# Block_Manager_Rev_D1.net
KiCad netlist of a schematic drawn in EAGLE
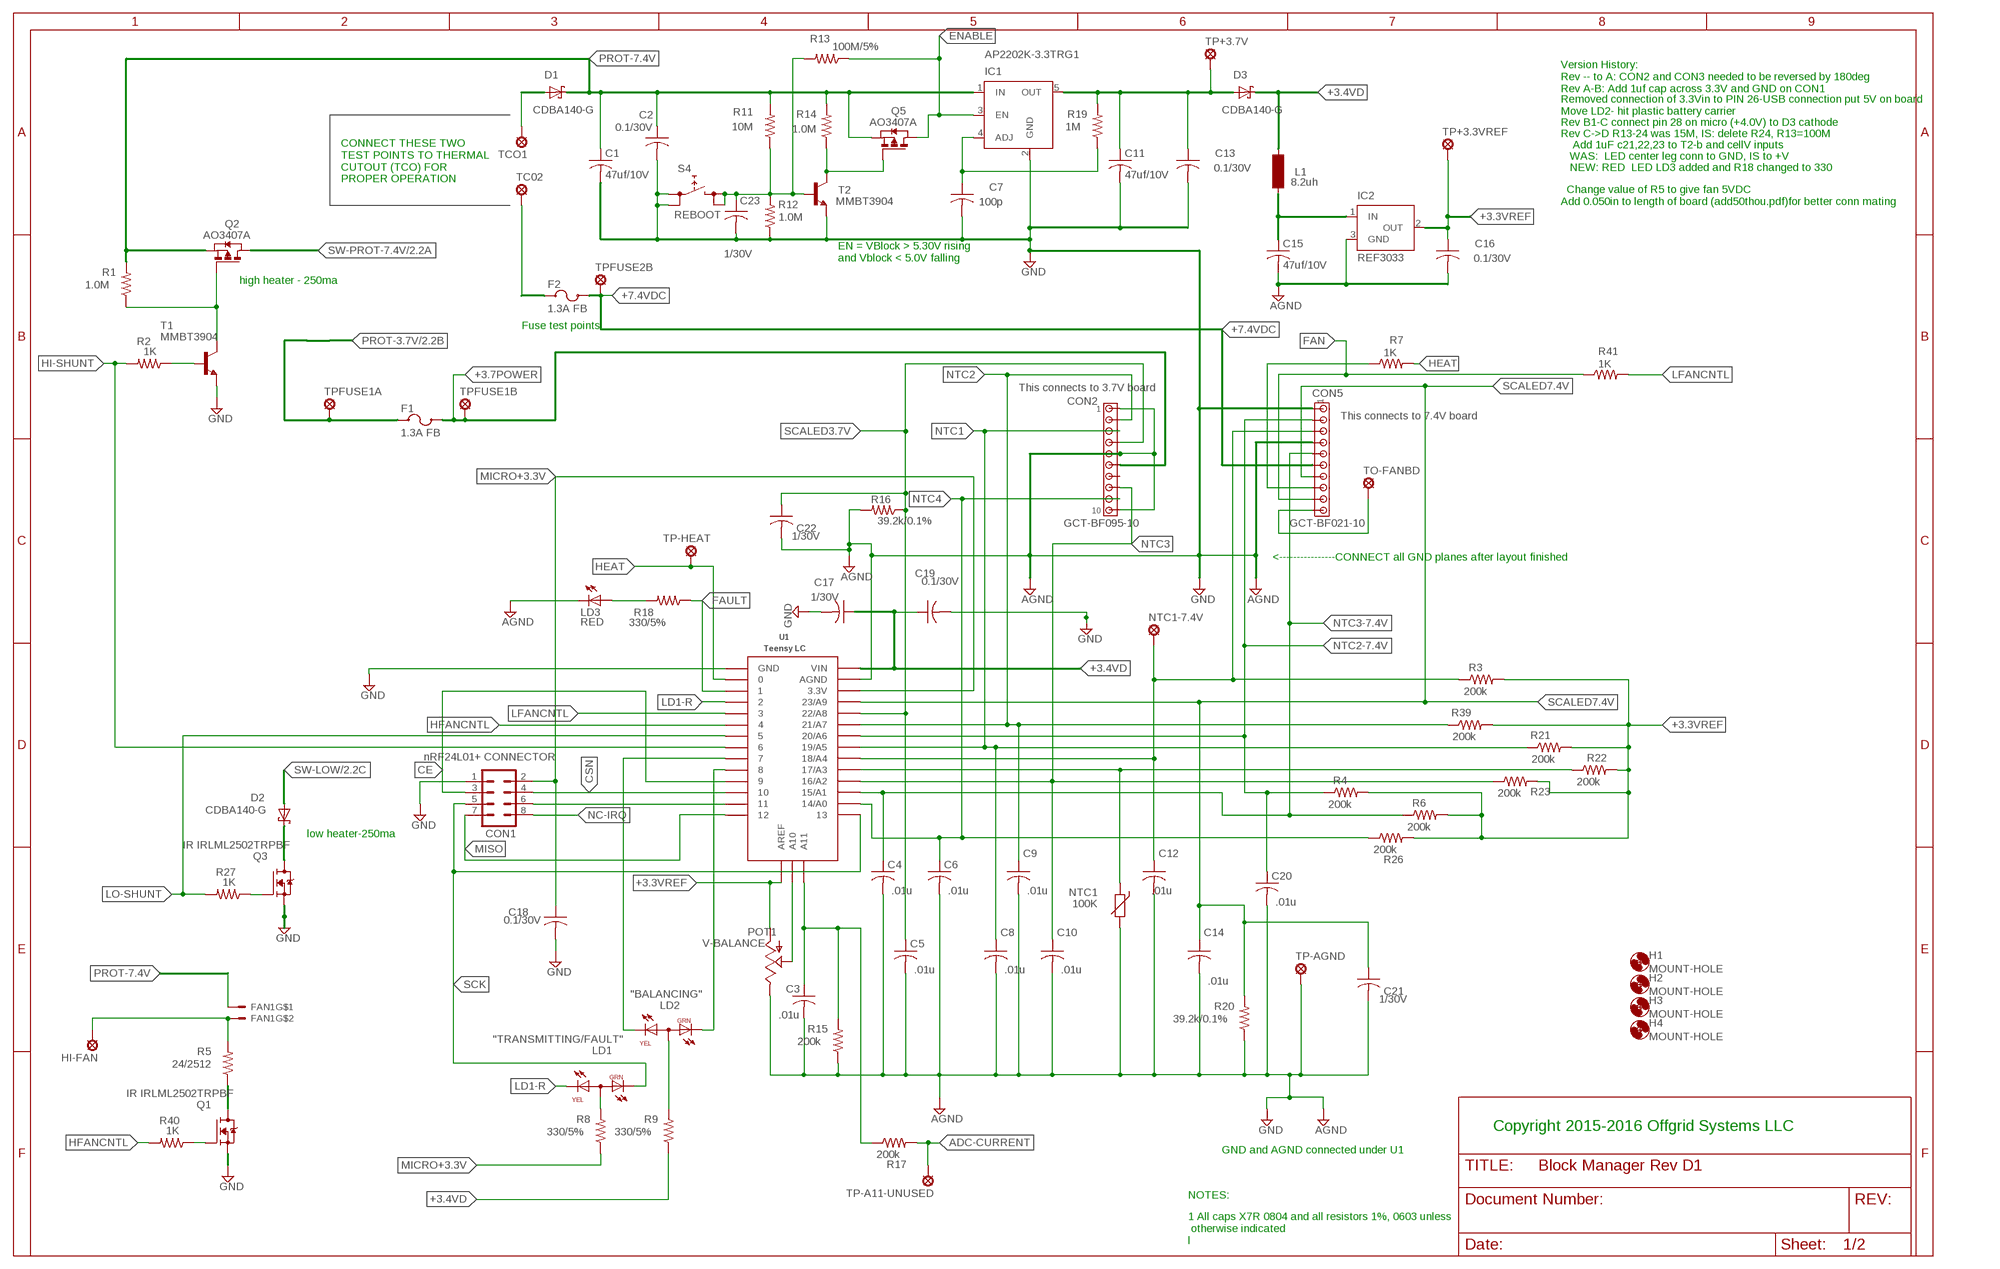
[diagram p0: schematic, sheet 1]
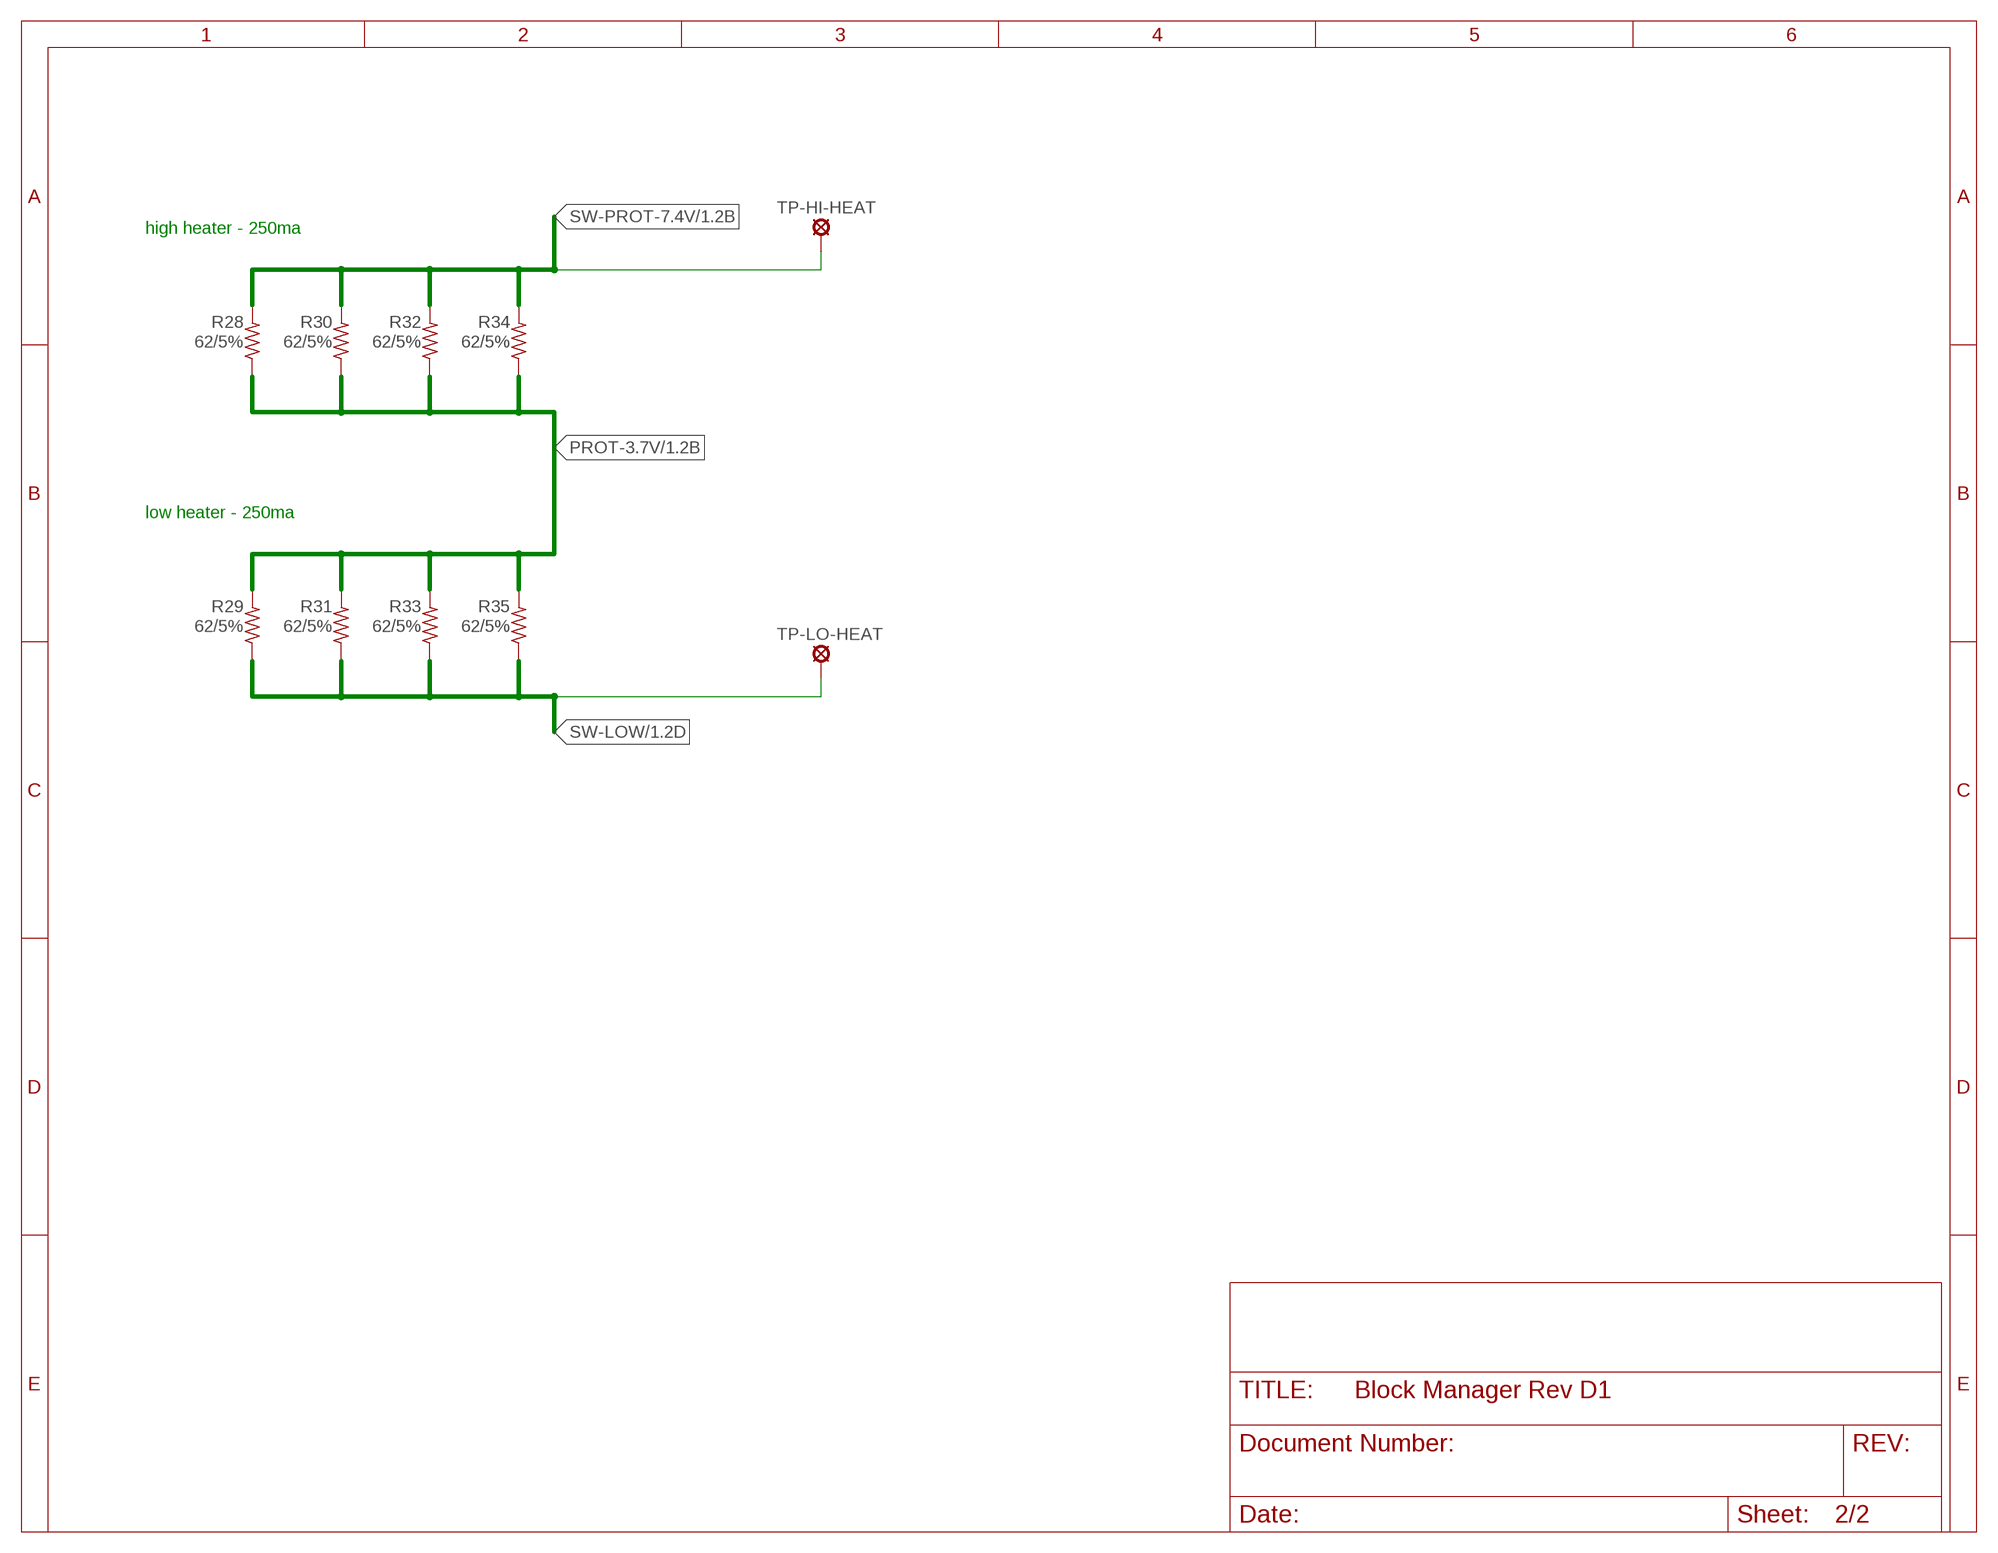
[diagram p1: schematic, sheet 2]

(export (version "E")
  (design (tool "Eeschema 10.0.6"))
  (components
    (comp (ref "C1")
      (value "47uf/10V")
      (footprint "eagle-import:C0805K")
      (fields (field (name "MPN") "Murata GRM21BR61A476ME15L"))
      (libsource (lib "eagle-import") (part "C-USC0805K"))
    )
    (comp (ref "C2")
      (value "0.1/30V")
      (footprint "eagle-import:TIMS_INDUCTOR_C0805")
      (fields (field (name "MPN") "Kemet C0805C104K5RACTU"))
      (libsource (lib "eagle-import") (part "TIMS_INDUCTOR_C-USC0805"))
    )
    (comp (ref "C3")
      (value ".01u")
      (footprint "eagle-import:TIMS_INDUCTOR_C0805")
      (fields (field (name "MPN") "Kemet C0805C103K5RACTU"))
      (libsource (lib "eagle-import") (part "TIMS_INDUCTOR_C-USC0805"))
    )
    (comp (ref "C4")
      (value ".01u")
      (footprint "eagle-import:TIMS_INDUCTOR_C0805")
      (fields (field (name "MPN") "Kemet C0805C103K5RACTU"))
      (libsource (lib "eagle-import") (part "TIMS_INDUCTOR_C-USC0805"))
    )
    (comp (ref "C5")
      (value ".01u")
      (footprint "eagle-import:TIMS_INDUCTOR_C0805")
      (fields (field (name "MPN") "Kemet C0805C103K5RACTU"))
      (libsource (lib "eagle-import") (part "TIMS_INDUCTOR_C-USC0805"))
    )
    (comp (ref "C6")
      (value ".01u")
      (footprint "eagle-import:TIMS_INDUCTOR_C0805")
      (fields (field (name "MPN") "Kemet C0805C103K5RACTU"))
      (libsource (lib "eagle-import") (part "TIMS_INDUCTOR_C-USC0805"))
    )
    (comp (ref "C7")
      (value "100p")
      (footprint "eagle-import:TIMS_INDUCTOR_C0805")
      (fields (field (name "MPN") "Kemet C0805C104K5RACTU"))
      (libsource (lib "eagle-import") (part "TIMS_INDUCTOR_C-USC0805"))
    )
    (comp (ref "C8")
      (value ".01u")
      (footprint "eagle-import:TIMS_INDUCTOR_C0805")
      (fields (field (name "MPN") "Kemet C0805C103K5RACTU"))
      (libsource (lib "eagle-import") (part "TIMS_INDUCTOR_C-USC0805"))
    )
    (comp (ref "C9")
      (value ".01u")
      (footprint "eagle-import:TIMS_INDUCTOR_C0805")
      (fields (field (name "MPN") "Kemet C0805C103K5RACTU"))
      (libsource (lib "eagle-import") (part "TIMS_INDUCTOR_C-USC0805"))
    )
    (comp (ref "C10")
      (value ".01u")
      (footprint "eagle-import:TIMS_INDUCTOR_C0805")
      (fields (field (name "MPN") "Kemet C0805C103K5RACTU"))
      (libsource (lib "eagle-import") (part "TIMS_INDUCTOR_C-USC0805"))
    )
    (comp (ref "C11")
      (value "47uf/10V")
      (footprint "eagle-import:C0805K")
      (fields (field (name "MPN") "Murata GRM21BR61A476ME15L"))
      (libsource (lib "eagle-import") (part "C-USC0805K"))
    )
    (comp (ref "C12")
      (value ".01u")
      (footprint "eagle-import:TIMS_INDUCTOR_C0805")
      (fields (field (name "MPN") "Kemet C0805C103K5RACTU"))
      (libsource (lib "eagle-import") (part "TIMS_INDUCTOR_C-USC0805"))
    )
    (comp (ref "C13")
      (value "0.1/30V")
      (footprint "eagle-import:TIMS_INDUCTOR_C0805")
      (fields (field (name "MPN") "Kemet C0805C104K5RACTU"))
      (libsource (lib "eagle-import") (part "TIMS_INDUCTOR_C-USC0805"))
    )
    (comp (ref "C14")
      (value ".01u")
      (footprint "eagle-import:TIMS_INDUCTOR_C0805")
      (fields (field (name "MPN") "Kemet C0805C103K5RACTU"))
      (libsource (lib "eagle-import") (part "TIMS_INDUCTOR_C-USC0805"))
    )
    (comp (ref "C15")
      (value "47uf/10V")
      (footprint "eagle-import:C0805K")
      (fields (field (name "MPN") "Murata GRM21BR61A476ME15L"))
      (libsource (lib "eagle-import") (part "C-USC0805K"))
    )
    (comp (ref "C16")
      (value "0.1/30V")
      (footprint "eagle-import:TIMS_INDUCTOR_C0805")
      (fields (field (name "MPN") "Kemet C0805C104K5RACTU"))
      (libsource (lib "eagle-import") (part "TIMS_INDUCTOR_C-USC0805"))
    )
    (comp (ref "C17")
      (value "1/30V")
      (footprint "eagle-import:TIMS_INDUCTOR_C0805")
      (fields (field (name "MPN") "Kemet C0805C104K5RACTU"))
      (libsource (lib "eagle-import") (part "TIMS_INDUCTOR_C-USC0805"))
    )
    (comp (ref "C18")
      (value "0.1/30V")
      (footprint "eagle-import:TIMS_INDUCTOR_C0805")
      (fields (field (name "MPN") "Kemet C0805C103K5RACTU"))
      (libsource (lib "eagle-import") (part "TIMS_INDUCTOR_C-USC0805"))
    )
    (comp (ref "C19")
      (value "0.1/30V")
      (footprint "eagle-import:TIMS_INDUCTOR_C0805")
      (fields (field (name "MPN") "Kemet C0805C103K5RACTU"))
      (libsource (lib "eagle-import") (part "TIMS_INDUCTOR_C-USC0805"))
    )
    (comp (ref "C20")
      (value ".01u")
      (footprint "eagle-import:TIMS_INDUCTOR_C0805")
      (fields (field (name "MPN") "Kemet C0805C103K5RACTU"))
      (libsource (lib "eagle-import") (part "TIMS_INDUCTOR_C-USC0805"))
    )
    (comp (ref "C21")
      (value "1/30V")
      (footprint "eagle-import:TIMS_INDUCTOR_C0805")
      (fields (field (name "MPN") "Kemet C0805C104K5RACTU"))
      (libsource (lib "eagle-import") (part "TIMS_INDUCTOR_C-USC0805"))
    )
    (comp (ref "C22")
      (value "1/30V")
      (footprint "eagle-import:TIMS_INDUCTOR_C0805")
      (fields (field (name "MPN") "Kemet C0805C104K5RACTU"))
      (libsource (lib "eagle-import") (part "TIMS_INDUCTOR_C-USC0805"))
    )
    (comp (ref "C23")
      (value "1/30V")
      (footprint "eagle-import:TIMS_INDUCTOR_C0805")
      (fields (field (name "MPN") "Kemet C0805C104K5RACTU"))
      (libsource (lib "eagle-import") (part "TIMS_INDUCTOR_C-USC0805"))
    )
    (comp (ref "CON1")
      (value "nRF24L01+ CONNECTOR")
      (footprint "eagle-import:MA04-2")
      (fields (field (name "MPN") "Precidip 803-87-008-10-012101"))
      (libsource (lib "eagle-import") (part "MA04-2"))
    )
    (comp (ref "CON2")
      (value "GCT-BF095-10")
      (footprint "eagle-import:GCT-BF085-10")
      (libsource (lib "eagle-import") (part "GCT-BF095-10"))
    )
    (comp (ref "CON5")
      (value "GCT-BF021-10")
      (footprint "eagle-import:GCT-BF021-10")
      (libsource (lib "eagle-import") (part "GCT-BF021-10"))
    )
    (comp (ref "D1")
      (value "CDBA140-G")
      (footprint "eagle-import:DO214AC")
      (fields (field (name "MPN") "comchip CDBA140-G"))
      (libsource (lib "eagle-import") (part "CDBA140-G"))
    )
    (comp (ref "D2")
      (value "CDBA140-G")
      (footprint "eagle-import:DO214AC")
      (fields (field (name "MPN") "comchip CDBA140-G"))
      (libsource (lib "eagle-import") (part "CDBA140-G"))
    )
    (comp (ref "D3")
      (value "CDBA140-G")
      (footprint "eagle-import:DO214AC")
      (fields (field (name "MPN") "comchip CDBA140-G"))
      (libsource (lib "eagle-import") (part "CDBA140-G"))
    )
    (comp (ref "F1")
      (value "1.3A FB")
      (footprint "eagle-import:TE-0603SFV125F")
      (fields (field (name "MPN") "TE 0603SFV125F/32-2"))
      (libsource (lib "eagle-import") (part "TE-0603SFV125F"))
    )
    (comp (ref "F2")
      (value "1.3A FB")
      (footprint "eagle-import:TE-0603SFV125F")
      (fields (field (name "MPN") "TE 0603SFV125F"))
      (libsource (lib "eagle-import") (part "TE-0603SFV125F"))
    )
    (comp (ref "FAN1")
      (value "30mm fan")
      (footprint "eagle-import:30X30MMFAN")
      (fields (field (name "MPN-FAN") "TBD"))
      (libsource (lib "eagle-import") (part "30X30MMFAN"))
    )
    (comp (ref "H1")
      (value "MOUNT-HOLE")
      (footprint "eagle-import:2,6")
      (libsource (lib "eagle-import") (part "MOUNT-HOLE"))
    )
    (comp (ref "H2")
      (value "MOUNT-HOLE")
      (footprint "eagle-import:2,6")
      (libsource (lib "eagle-import") (part "MOUNT-HOLE"))
    )
    (comp (ref "H3")
      (value "MOUNT-HOLE")
      (footprint "eagle-import:2,6")
      (libsource (lib "eagle-import") (part "MOUNT-HOLE"))
    )
    (comp (ref "H4")
      (value "MOUNT-HOLE")
      (footprint "eagle-import:2,6")
      (libsource (lib "eagle-import") (part "MOUNT-HOLE"))
    )
    (comp (ref "HI-FAN")
      (value "LSP10")
      (footprint "eagle-import:LSP10")
      (libsource (lib "eagle-import") (part "LSP10"))
    )
    (comp (ref "IC1")
      (value "AP2202K-3.3TRG1")
      (footprint "eagle-import:SOT23-5")
      (fields
        (field (name "MF") "ALTERA CORPORATION")
        (field (name "MPN") "MIC5219BM5 TR")
        (field (name "MF_1") "Diodes INc")
        (field (name "MPN_1") "Diodes AP2202K-3.3TRG1")
      )
      (libsource (lib "eagle-import") (part "MIC5205"))
    )
    (comp (ref "IC2")
      (value "REF3033")
      (footprint "eagle-import:SOT23")
      (fields
        (field (name "MF") "MAXIM")
        (field (name "MPN") "MAX6520EUR-T")
        (field (name "MPN_1") "TI REF3033AIDBZR")
      )
      (libsource (lib "eagle-import") (part "MAX6520"))
    )
    (comp (ref "L1")
      (value "8.2uh")
      (footprint "eagle-import:SM-1206")
      (fields (field (name "MPN") "Abracon AIML-1206-8R2K-T"))
      (libsource (lib "eagle-import") (part "SM-1206"))
    )
    (comp (ref "LD1")
      (value "\"TRANSMITTING/FAULT\"")
      (footprint "eagle-import:SUN-XZMDKVG56W")
      (fields (field (name "MPN") "Kingbright APBA3010SYKCGKC-GX"))
      (libsource (lib "eagle-import") (part "KINGBRIGHT-APBA3010"))
    )
    (comp (ref "LD2")
      (value "\"BALANCING\"")
      (footprint "eagle-import:SUN-XZMDKVG56W")
      (fields (field (name "MPN") "Kingbright APBA3010SYKCGKC-GX"))
      (libsource (lib "eagle-import") (part "KINGBRIGHT-APBA3010"))
    )
    (comp (ref "LD3")
      (value "RED")
      (footprint "eagle-import:LITEON-LTST-S270KRKT")
      (fields (field (name "MPN") "LITEON-LTST-S270KRKT"))
      (libsource (lib "eagle-import") (part "LITEON-LTST-S270KRKT"))
    )
    (comp (ref "NTC1")
      (value "100K")
      (footprint "eagle-import:0603")
      (fields (field (name "MPN") "MURATA NCP18WF104J03RB"))
      (libsource (lib "eagle-import") (part "NTC-MURATA-NCP18WF104J03RB"))
    )
    (comp (ref "NTC1-7.4V")
      (value "LSP10")
      (footprint "eagle-import:LSP10")
      (libsource (lib "eagle-import") (part "LSP10"))
    )
    (comp (ref "POT1")
      (value "V-BALANCE")
      (footprint "eagle-import:BOURNS-3361-RA")
      (fields (field (name "MPN") "Bourns 3361S-1-104GLF"))
      (libsource (lib "eagle-import") (part "BOURNS-3361-RA"))
    )
    (comp (ref "Q1")
      (value "IRLML2502TRPBF")
      (footprint "eagle-import:SOT23")
      (fields (field (name "MPN") "IR IRLML2502TRPBF"))
      (libsource (lib "eagle-import") (part "IRLML2060TRPBF"))
    )
    (comp (ref "Q2")
      (value "AO3407A")
      (footprint "eagle-import:SOT23-BIGPADS")
      (fields (field (name "MPN") "Alpha AO3407A"))
      (libsource (lib "eagle-import") (part "AO3407A"))
    )
    (comp (ref "Q3")
      (value "IRLML2502TRPBF")
      (footprint "eagle-import:SOT23")
      (fields (field (name "MPN") "IR IRLML2502TRPBF"))
      (libsource (lib "eagle-import") (part "IRLML2060TRPBF"))
    )
    (comp (ref "Q5")
      (value "AO3407A")
      (footprint "eagle-import:SOT23-BIGPADS")
      (libsource (lib "eagle-import") (part "AO3407A"))
    )
    (comp (ref "R1")
      (value "1.0M")
      (footprint "eagle-import:R0603")
      (fields (field (name "MPN") "Bourns CR0603-FX-1004ELF"))
      (libsource (lib "eagle-import") (part "R-US_R0603"))
    )
    (comp (ref "R2")
      (value "1K")
      (footprint "eagle-import:R0603")
      (fields (field (name "MPN") "Bourns CR0603-FX-1001ELF"))
      (libsource (lib "eagle-import") (part "R-US_R0603"))
    )
    (comp (ref "R3")
      (value "200k")
      (footprint "eagle-import:R0603")
      (fields (field (name "MPN") "Bourns CR0603-FX-2003ELF"))
      (libsource (lib "eagle-import") (part "R-US_R0603"))
    )
    (comp (ref "R4")
      (value "200k")
      (footprint "eagle-import:R0603")
      (fields (field (name "MPN") "Bourns CR0603-FX-2003ELF"))
      (libsource (lib "eagle-import") (part "R-US_R0603"))
    )
    (comp (ref "R5")
      (value "24/2512")
      (footprint "eagle-import:R2512")
      (fields (field (name "MPN") "Rohm MCR100JZHJ240"))
      (libsource (lib "eagle-import") (part "R-US_R2512"))
    )
    (comp (ref "R6")
      (value "200k")
      (footprint "eagle-import:R0603")
      (fields (field (name "MPN") "Bourns CR0603-FX-2003ELF"))
      (libsource (lib "eagle-import") (part "R-US_R0603"))
    )
    (comp (ref "R7")
      (value "1K")
      (footprint "eagle-import:R0603")
      (fields (field (name "MPN") "Bourns CR0603-FX-1001ELF"))
      (libsource (lib "eagle-import") (part "R-US_R0603"))
    )
    (comp (ref "R8")
      (value "330/5%")
      (footprint "eagle-import:R0603")
      (fields (field (name "MPN") "Bourns CR0603-JW-331ELF"))
      (libsource (lib "eagle-import") (part "R-US_R0603"))
    )
    (comp (ref "R9")
      (value "330/5%")
      (footprint "eagle-import:R0603")
      (fields (field (name "MPN") "Bourns CR0603-JW-331ELF"))
      (libsource (lib "eagle-import") (part "R-US_R0603"))
    )
    (comp (ref "R11")
      (value "10M")
      (footprint "eagle-import:R0603")
      (fields (field (name "MPN") "Bourns CR0603-JW-106ELF"))
      (libsource (lib "eagle-import") (part "R-US_R0603"))
    )
    (comp (ref "R12")
      (value "1.0M")
      (footprint "eagle-import:R0603")
      (fields (field (name "MPN") "Bourns CR0603-FX-1004ELF"))
      (libsource (lib "eagle-import") (part "R-US_R0603"))
    )
    (comp (ref "R13")
      (value "100M/5%")
      (footprint "eagle-import:R0603")
      (fields (field (name "MPN") "Stackpole HMC0603JT100M"))
      (libsource (lib "eagle-import") (part "R-US_R0603"))
    )
    (comp (ref "R14")
      (value "1.0M")
      (footprint "eagle-import:R0603")
      (fields (field (name "MPN") "Bourns CR0603-FX-1004ELF"))
      (libsource (lib "eagle-import") (part "R-US_R0603"))
    )
    (comp (ref "R15")
      (value "200k")
      (footprint "eagle-import:R0603")
      (fields (field (name "MPN") "Bourns CR0603-FX-2003ELF"))
      (libsource (lib "eagle-import") (part "R-US_R0603"))
    )
    (comp (ref "R16")
      (value "39.2k/0.1%")
      (footprint "eagle-import:R0603")
      (fields (field (name "MPN") "Susumu RG1608P-3922-B-T5"))
      (libsource (lib "eagle-import") (part "R-US_R0603"))
    )
    (comp (ref "R17")
      (value "200k")
      (footprint "eagle-import:R0603")
      (fields (field (name "MPN") "Bourns CR0603-FX-2003ELF"))
      (libsource (lib "eagle-import") (part "R-US_R0603"))
    )
    (comp (ref "R18")
      (value "330/5%")
      (footprint "eagle-import:R0603")
      (fields (field (name "MPN") "Bourns CR0603-FX-2003ELF"))
      (libsource (lib "eagle-import") (part "R-US_R0603"))
    )
    (comp (ref "R19")
      (value "1M")
      (footprint "eagle-import:R0603")
      (fields (field (name "MPN") "Bourns CR0603-FX-1004ELF"))
      (libsource (lib "eagle-import") (part "R-US_R0603"))
    )
    (comp (ref "R20")
      (value "39.2k/0.1%")
      (footprint "eagle-import:R0603")
      (fields (field (name "MPN") "Susumu RG1608P-3922-B-T5"))
      (libsource (lib "eagle-import") (part "R-US_R0603"))
    )
    (comp (ref "R21")
      (value "200k")
      (footprint "eagle-import:R0603")
      (fields (field (name "MPN") "Bourns CR0603-FX-2003ELF"))
      (libsource (lib "eagle-import") (part "R-US_R0603"))
    )
    (comp (ref "R22")
      (value "200k")
      (footprint "eagle-import:R0603")
      (fields (field (name "MPN") "Bourns CR0603-FX-2003ELF"))
      (libsource (lib "eagle-import") (part "R-US_R0603"))
    )
    (comp (ref "R23")
      (value "200k")
      (footprint "eagle-import:R0603")
      (fields (field (name "MPN") "Bourns CR0603-FX-2003ELF"))
      (libsource (lib "eagle-import") (part "R-US_R0603"))
    )
    (comp (ref "R26")
      (value "200k")
      (footprint "eagle-import:R0603")
      (fields (field (name "MPN") "Bourns CR0603-FX-2003ELF"))
      (libsource (lib "eagle-import") (part "R-US_R0603"))
    )
    (comp (ref "R27")
      (value "1K")
      (footprint "eagle-import:R0603")
      (fields (field (name "MPN") "Bourns CR0603-FX-1001ELF"))
      (libsource (lib "eagle-import") (part "R-US_R0603"))
    )
    (comp (ref "R39")
      (value "200k")
      (footprint "eagle-import:R0603")
      (fields (field (name "MPN") "Bourns CR0603-FX-2003ELF"))
      (libsource (lib "eagle-import") (part "R-US_R0603"))
    )
    (comp (ref "R40")
      (value "1K")
      (footprint "eagle-import:R0603")
      (fields (field (name "MPN") "Bourns CR0603-FX-1001ELF"))
      (libsource (lib "eagle-import") (part "R-US_R0603"))
    )
    (comp (ref "R41")
      (value "1K")
      (footprint "eagle-import:R0603")
      (fields (field (name "MPN") "Bourns CR0603-FX-1001ELF"))
      (libsource (lib "eagle-import") (part "R-US_R0603"))
    )
    (comp (ref "S4")
      (value "REBOOT")
      (footprint "eagle-import:PTS645")
      (fields (field (name "MPN") "C&k PTS645SM43SMTR92 LFS"))
      (libsource (lib "eagle-import") (part "PTS645"))
    )
    (comp (ref "T1")
      (value "MMBT3904")
      (footprint "eagle-import:SOT23-BEC")
      (fields (field (name "MPN") "NXP MMBT3904,215"))
      (libsource (lib "eagle-import") (part "-NPN-SOT23-BECMMBT3904LT1"))
    )
    (comp (ref "T2")
      (value "MMBT3904")
      (footprint "eagle-import:SOT23-BEC")
      (fields (field (name "MPN") "NXP MMBT3904,215"))
      (libsource (lib "eagle-import") (part "-NPN-SOT23-BECMMBT3904LT1"))
    )
    (comp (ref "TC02")
      (value "SOLPAD1.2MMDRILL")
      (footprint "eagle-import:SOLPADWITH1.2MMDRILL")
      (libsource (lib "eagle-import") (part "SOLPAD1.2MMDRILL"))
    )
    (comp (ref "TCO1")
      (value "SOLPAD1.2MMDRILL")
      (footprint "eagle-import:SOLPADWITH1.2MMDRILL")
      (libsource (lib "eagle-import") (part "SOLPAD1.2MMDRILL"))
    )
    (comp (ref "TO-FANBD")
      (value "LSP10")
      (footprint "eagle-import:LSP10")
      (libsource (lib "eagle-import") (part "LSP10"))
    )
    (comp (ref "TP+3.3VREF")
      (value "LSP10")
      (footprint "eagle-import:LSP10")
      (libsource (lib "eagle-import") (part "LSP10"))
    )
    (comp (ref "TP+3.7V")
      (value "LSP10")
      (footprint "eagle-import:LSP10")
      (libsource (lib "eagle-import") (part "LSP10"))
    )
    (comp (ref "TP-A11-UNUSED")
      (value "LSP10")
      (footprint "eagle-import:LSP10")
      (libsource (lib "eagle-import") (part "LSP10"))
    )
    (comp (ref "TP-AGND")
      (value "LSP10")
      (footprint "eagle-import:LSP10")
      (libsource (lib "eagle-import") (part "LSP10"))
    )
    (comp (ref "TP-HEAT")
      (value "LSP10")
      (footprint "eagle-import:LSP10")
      (libsource (lib "eagle-import") (part "LSP10"))
    )
    (comp (ref "TPFUSE1A")
      (value "LSP10")
      (footprint "eagle-import:LSP10")
      (libsource (lib "eagle-import") (part "LSP10"))
    )
    (comp (ref "TPFUSE1B")
      (value "LSP10")
      (footprint "eagle-import:LSP10")
      (libsource (lib "eagle-import") (part "LSP10"))
    )
    (comp (ref "TPFUSE2B")
      (value "LSP10")
      (footprint "eagle-import:LSP10")
      (libsource (lib "eagle-import") (part "LSP10"))
    )
    (comp (ref "U1")
      (value "Teensy LC")
      (footprint "eagle-import:TEENSY_3.0-DIP+ANALOG")
      (fields (field (name "MPN") "OshPark Teensy 3.1"))
      (libsource (lib "eagle-import") (part "TEENSY_3.0-DIP+ANALOG"))
    )
    (comp (ref "R28")
      (value "62/5%")
      (footprint "eagle-import:R2512")
      (fields (field (name "MPN") "Rohm MCR100JZHJ620"))
      (libsource (lib "eagle-import") (part "R-US_R2512"))
    )
    (comp (ref "R29")
      (value "62/5%")
      (footprint "eagle-import:R2512")
      (fields (field (name "MPN") "Rohm MCR100JZHJ620"))
      (libsource (lib "eagle-import") (part "R-US_R2512"))
    )
    (comp (ref "R30")
      (value "62/5%")
      (footprint "eagle-import:R2512")
      (fields (field (name "MPN") "Rohm MCR100JZHJ620"))
      (libsource (lib "eagle-import") (part "R-US_R2512"))
    )
    (comp (ref "R31")
      (value "62/5%")
      (footprint "eagle-import:R2512")
      (fields (field (name "MPN") "Rohm MCR100JZHJ620"))
      (libsource (lib "eagle-import") (part "R-US_R2512"))
    )
    (comp (ref "R32")
      (value "62/5%")
      (footprint "eagle-import:R2512")
      (fields (field (name "MPN") "Rohm MCR100JZHJ620"))
      (libsource (lib "eagle-import") (part "R-US_R2512"))
    )
    (comp (ref "R33")
      (value "62/5%")
      (footprint "eagle-import:R2512")
      (fields (field (name "MPN") "Rohm MCR100JZHJ620"))
      (libsource (lib "eagle-import") (part "R-US_R2512"))
    )
    (comp (ref "R34")
      (value "62/5%")
      (footprint "eagle-import:R2512")
      (fields (field (name "MPN") "Rohm MCR100JZHJ620"))
      (libsource (lib "eagle-import") (part "R-US_R2512"))
    )
    (comp (ref "R35")
      (value "62/5%")
      (footprint "eagle-import:R2512")
      (fields (field (name "MPN") "Rohm MCR100JZHJ620"))
      (libsource (lib "eagle-import") (part "R-US_R2512"))
    )
    (comp (ref "TP-HI-HEAT")
      (value "LSP10")
      (footprint "eagle-import:LSP10")
      (libsource (lib "eagle-import") (part "LSP10"))
    )
    (comp (ref "TP-LO-HEAT")
      (value "LSP10")
      (footprint "eagle-import:LSP10")
      (libsource (lib "eagle-import") (part "LSP10"))
    )
  )
  (nets
    (net (code "1") (name "+3.3VREF") (class "Default")
      (node (ref "C16") (pin "1") (pinfunction "1_1") (pintype "passive"))
      (node (ref "IC2") (pin "2") (pinfunction "OUT_2") (pintype "output"))
      (node (ref "POT1") (pin "1") (pinfunction "A_1") (pintype "passive"))
      (node (ref "R21") (pin "2") (pinfunction "2_2") (pintype "passive"))
      (node (ref "R22") (pin "2") (pinfunction "2_2") (pintype "passive"))
      (node (ref "R23") (pin "2") (pinfunction "2_2") (pintype "passive"))
      (node (ref "R26") (pin "2") (pinfunction "2_2") (pintype "passive"))
      (node (ref "R3") (pin "2") (pinfunction "2_2") (pintype "passive"))
      (node (ref "R39") (pin "2") (pinfunction "2_2") (pintype "passive"))
      (node (ref "R4") (pin "2") (pinfunction "2_2") (pintype "passive"))
      (node (ref "R6") (pin "2") (pinfunction "2_2") (pintype "passive"))
      (node (ref "TP+3.3VREF") (pin "MP") (pinfunction "MP_MP") (pintype "passive"))
      (node (ref "U1") (pin "AREF") (pinfunction "AREF_AREF") (pintype "power_in"))
    )
    (net (code "2") (name "+3.4VD") (class "Default")
      (node (ref "C17") (pin "1") (pinfunction "1_1") (pintype "passive"))
      (node (ref "C19") (pin "1") (pinfunction "1_1") (pintype "passive"))
      (node (ref "D3") (pin "C") (pinfunction "C_C") (pintype "passive"))
      (node (ref "L1") (pin "2") (pinfunction "2_2") (pintype "passive"))
      (node (ref "R9") (pin "1") (pinfunction "1_1") (pintype "passive"))
      (node (ref "U1") (pin "VIN") (pinfunction "VIN_VIN") (pintype "power_in"))
    )
    (net (code "3") (name "+3.7POWER") (class "Default")
      (node (ref "CON2") (pin "P$6") (pinfunction "6_P$6") (pintype "passive"))
      (node (ref "F1") (pin "P$2") (pinfunction "2A_P$2") (pintype "passive"))
      (node (ref "TPFUSE1B") (pin "MP") (pinfunction "MP_MP") (pintype "passive"))
    )
    (net (code "4") (name "+7.4VDC") (class "Default")
      (node (ref "CON5") (pin "P$6") (pinfunction "6_P$6") (pintype "passive"))
      (node (ref "F2") (pin "P$2") (pinfunction "2A_P$2") (pintype "passive"))
      (node (ref "TPFUSE2B") (pin "MP") (pinfunction "MP_MP") (pintype "passive"))
    )
    (net (code "5") (name "ADC-CURRENT") (class "Default")
      (node (ref "R17") (pin "2") (pinfunction "2_2") (pintype "passive"))
      (node (ref "TP-A11-UNUSED") (pin "MP") (pinfunction "MP_MP") (pintype "passive"))
    )
    (net (code "6") (name "CE") (class "Default")
      (node (ref "CON1") (pin "3") (pinfunction "3_3") (pintype "passive"))
      (node (ref "U1") (pin "9") (pinfunction "9_9") (pintype "bidirectional"))
    )
    (net (code "7") (name "CSN") (class "Default")
      (node (ref "CON1") (pin "4") (pinfunction "4_4") (pintype "passive"))
      (node (ref "U1") (pin "10") (pinfunction "10_10") (pintype "bidirectional"))
    )
    (net (code "8") (name "ENABLE") (class "Default")
      (node (ref "IC1") (pin "3") (pinfunction "EN_3") (pintype "input"))
      (node (ref "Q5") (pin "2") (pinfunction "D_2") (pintype "passive"))
      (node (ref "R13") (pin "1") (pinfunction "1_1") (pintype "passive"))
    )
    (net (code "9") (name "FAN") (class "Default")
      (node (ref "CON5") (pin "P$9") (pinfunction "9_P$9") (pintype "passive"))
      (node (ref "R41") (pin "1") (pinfunction "1_1") (pintype "passive"))
    )
    (net (code "10") (name "FAULT") (class "Default")
      (node (ref "R18") (pin "1") (pinfunction "1_1") (pintype "passive"))
      (node (ref "U1") (pin "1") (pinfunction "1_1") (pintype "bidirectional"))
    )
    (net (code "11") (name "GND") (class "Default")
      (node (ref "C1") (pin "2") (pinfunction "2_2") (pintype "passive"))
      (node (ref "C10") (pin "2") (pinfunction "2_2") (pintype "passive"))
      (node (ref "C11") (pin "2") (pinfunction "2_2") (pintype "passive"))
      (node (ref "C12") (pin "2") (pinfunction "2_2") (pintype "passive"))
      (node (ref "C13") (pin "2") (pinfunction "2_2") (pintype "passive"))
      (node (ref "C14") (pin "2") (pinfunction "2_2") (pintype "passive"))
      (node (ref "C15") (pin "2") (pinfunction "2_2") (pintype "passive"))
      (node (ref "C16") (pin "2") (pinfunction "2_2") (pintype "passive"))
      (node (ref "C17") (pin "2") (pinfunction "2_2") (pintype "passive"))
      (node (ref "C18") (pin "2") (pinfunction "2_2") (pintype "passive"))
      (node (ref "C19") (pin "2") (pinfunction "2_2") (pintype "passive"))
      (node (ref "C2") (pin "2") (pinfunction "2_2") (pintype "passive"))
      (node (ref "C20") (pin "2") (pinfunction "2_2") (pintype "passive"))
      (node (ref "C21") (pin "2") (pinfunction "2_2") (pintype "passive"))
      (node (ref "C22") (pin "2") (pinfunction "2_2") (pintype "passive"))
      (node (ref "C23") (pin "2") (pinfunction "2_2") (pintype "passive"))
      (node (ref "C3") (pin "2") (pinfunction "2_2") (pintype "passive"))
      (node (ref "C4") (pin "2") (pinfunction "2_2") (pintype "passive"))
      (node (ref "C5") (pin "2") (pinfunction "2_2") (pintype "passive"))
      (node (ref "C6") (pin "2") (pinfunction "2_2") (pintype "passive"))
      (node (ref "C7") (pin "2") (pinfunction "2_2") (pintype "passive"))
      (node (ref "C8") (pin "2") (pinfunction "2_2") (pintype "passive"))
      (node (ref "C9") (pin "2") (pinfunction "2_2") (pintype "passive"))
      (node (ref "CON1") (pin "1") (pinfunction "1_1") (pintype "passive"))
      (node (ref "CON2") (pin "P$1") (pinfunction "1_P$1") (pintype "passive"))
      (node (ref "CON2") (pin "P$10") (pinfunction "10_P$10") (pintype "passive"))
      (node (ref "CON2") (pin "P$5") (pinfunction "5_P$5") (pintype "passive"))
      (node (ref "CON5") (pin "P$1") (pinfunction "1_P$1") (pintype "passive"))
      (node (ref "CON5") (pin "P$4") (pinfunction "4_P$4") (pintype "passive"))
      (node (ref "IC1") (pin "2") (pinfunction "GND_2") (pintype "power_in"))
      (node (ref "IC2") (pin "3") (pinfunction "GND_3") (pintype "power_in"))
      (node (ref "LD3") (pin "CATHODE") (pinfunction "C_CATHODE") (pintype "passive"))
      (node (ref "NTC1") (pin "2") (pinfunction "2_2") (pintype "passive"))
      (node (ref "POT1") (pin "3") (pinfunction "E_3") (pintype "passive"))
      (node (ref "Q1") (pin "2") (pinfunction "S_2") (pintype "passive"))
      (node (ref "Q3") (pin "2") (pinfunction "S_2") (pintype "passive"))
      (node (ref "R12") (pin "1") (pinfunction "1_1") (pintype "passive"))
      (node (ref "R15") (pin "1") (pinfunction "1_1") (pintype "passive"))
      (node (ref "R16") (pin "2") (pinfunction "2_2") (pintype "passive"))
      (node (ref "R20") (pin "1") (pinfunction "1_1") (pintype "passive"))
      (node (ref "S4") (pin "1") (pinfunction "1_1") (pintype "passive"))
      (node (ref "S4") (pin "2") (pinfunction "2_2") (pintype "passive"))
      (node (ref "T1") (pin "E") (pinfunction "E_E") (pintype "passive"))
      (node (ref "T2") (pin "E") (pinfunction "E_E") (pintype "passive"))
      (node (ref "TP-AGND") (pin "MP") (pinfunction "MP_MP") (pintype "passive"))
      (node (ref "U1") (pin "AGND") (pinfunction "AGND_AGND") (pintype "power_in"))
      (node (ref "U1") (pin "GND") (pinfunction "GND_GND") (pintype "power_in"))
    )
    (net (code "12") (name "HEAT") (class "Default")
      (node (ref "R7") (pin "2") (pinfunction "2_2") (pintype "passive"))
      (node (ref "TP-HEAT") (pin "MP") (pinfunction "MP_MP") (pintype "passive"))
      (node (ref "U1") (pin "0") (pinfunction "0_0") (pintype "bidirectional"))
    )
    (net (code "13") (name "HFANCNTL") (class "Default")
      (node (ref "R40") (pin "2") (pinfunction "2_2") (pintype "passive"))
      (node (ref "U1") (pin "4") (pinfunction "4_4") (pintype "bidirectional"))
    )
    (net (code "14") (name "HI-SHUNT") (class "Default")
      (node (ref "R2") (pin "2") (pinfunction "2_2") (pintype "passive"))
      (node (ref "U1") (pin "6") (pinfunction "6_6") (pintype "bidirectional"))
    )
    (net (code "15") (name "LD1-R") (class "Default")
      (node (ref "LD1") (pin "2-CATH-RED") (pinfunction "CR_2-CATH-RED") (pintype "passive"))
      (node (ref "U1") (pin "2") (pinfunction "2_2") (pintype "bidirectional"))
    )
    (net (code "16") (name "LFANCNTL") (class "Default")
      (node (ref "R41") (pin "2") (pinfunction "2_2") (pintype "passive"))
      (node (ref "U1") (pin "3") (pinfunction "3_3") (pintype "bidirectional"))
    )
    (net (code "17") (name "LO-SHUNT") (class "Default")
      (node (ref "R27") (pin "2") (pinfunction "2_2") (pintype "passive"))
      (node (ref "U1") (pin "5") (pinfunction "5_5") (pintype "bidirectional"))
    )
    (net (code "18") (name "MICRO+3.3V") (class "Default")
      (node (ref "C18") (pin "1") (pinfunction "1_1") (pintype "passive"))
      (node (ref "CON1") (pin "2") (pinfunction "2_2") (pintype "passive"))
      (node (ref "R8") (pin "1") (pinfunction "1_1") (pintype "passive"))
      (node (ref "U1") (pin "3.3V") (pinfunction "3.3V_3.3V") (pintype "power_in"))
    )
    (net (code "19") (name "MISO") (class "Default")
      (node (ref "CON1") (pin "7") (pinfunction "7_7") (pintype "passive"))
      (node (ref "U1") (pin "12") (pinfunction "12_12") (pintype "bidirectional"))
    )
    (net (code "20") (name "NC-IRQ") (class "Default")
      (node (ref "CON1") (pin "8") (pinfunction "8_8") (pintype "passive"))
    )
    (net (code "21") (name "NTC1") (class "Default")
      (node (ref "C8") (pin "1") (pinfunction "1_1") (pintype "passive"))
      (node (ref "CON2") (pin "P$3") (pinfunction "3_P$3") (pintype "passive"))
      (node (ref "R21") (pin "1") (pinfunction "1_1") (pintype "passive"))
      (node (ref "U1") (pin "19/A5") (pinfunction "19/A5_19/A5") (pintype "bidirectional"))
    )
    (net (code "22") (name "NTC2") (class "Default")
      (node (ref "C9") (pin "1") (pinfunction "1_1") (pintype "passive"))
      (node (ref "CON2") (pin "P$2") (pinfunction "2_P$2") (pintype "passive"))
      (node (ref "R39") (pin "1") (pinfunction "1_1") (pintype "passive"))
      (node (ref "U1") (pin "21/A7") (pinfunction "21/A7_21/A7") (pintype "bidirectional"))
    )
    (net (code "23") (name "NTC2-7.4V") (class "Default")
      (node (ref "C20") (pin "1") (pinfunction "1_1") (pintype "passive"))
      (node (ref "CON5") (pin "P$2") (pinfunction "2_P$2") (pintype "passive"))
      (node (ref "R4") (pin "1") (pinfunction "1_1") (pintype "passive"))
      (node (ref "U1") (pin "20/A6") (pinfunction "20/A6_20/A6") (pintype "bidirectional"))
    )
    (net (code "24") (name "NTC3") (class "Default")
      (node (ref "C10") (pin "1") (pinfunction "1_1") (pintype "passive"))
      (node (ref "CON2") (pin "P$8") (pinfunction "8_P$8") (pintype "passive"))
      (node (ref "R23") (pin "1") (pinfunction "1_1") (pintype "passive"))
      (node (ref "U1") (pin "16/A2") (pinfunction "16/A2_16/A2") (pintype "bidirectional"))
    )
    (net (code "25") (name "NTC3-7.4V") (class "Default")
      (node (ref "C4") (pin "1") (pinfunction "1_1") (pintype "passive"))
      (node (ref "CON5") (pin "P$5") (pinfunction "5_P$5") (pintype "passive"))
      (node (ref "R6") (pin "1") (pinfunction "1_1") (pintype "passive"))
      (node (ref "U1") (pin "15/A1") (pinfunction "15/A1_15/A1") (pintype "bidirectional"))
    )
    (net (code "26") (name "NTC4") (class "Default")
      (node (ref "C6") (pin "1") (pinfunction "1_1") (pintype "passive"))
      (node (ref "CON2") (pin "P$9") (pinfunction "9_P$9") (pintype "passive"))
      (node (ref "R26") (pin "1") (pinfunction "1_1") (pintype "passive"))
      (node (ref "U1") (pin "14/A0") (pinfunction "14/A0_14/A0") (pintype "bidirectional"))
    )
    (net (code "27") (name "Net-(C3-Pad1)") (class "Default")
      (node (ref "C3") (pin "1") (pinfunction "1_1") (pintype "passive"))
      (node (ref "R15") (pin "2") (pinfunction "2_2") (pintype "passive"))
      (node (ref "R17") (pin "1") (pinfunction "1_1") (pintype "passive"))
      (node (ref "U1") (pin "A11") (pinfunction "A11_A11") (pintype "input"))
    )
    (net (code "28") (name "Net-(C23-Pad1)") (class "Default")
      (node (ref "C23") (pin "1") (pinfunction "1_1") (pintype "passive"))
      (node (ref "R11") (pin "1") (pinfunction "1_1") (pintype "passive"))
      (node (ref "R12") (pin "2") (pinfunction "2_2") (pintype "passive"))
      (node (ref "R13") (pin "2") (pinfunction "2_2") (pintype "passive"))
      (node (ref "S4") (pin "3") (pinfunction "3_3") (pintype "passive"))
      (node (ref "S4") (pin "4") (pinfunction "4_4") (pintype "passive"))
      (node (ref "T2") (pin "B") (pinfunction "B_B") (pintype "passive"))
    )
    (net (code "29") (name "Net-(CON1-Pad6)") (class "Default")
      (node (ref "CON1") (pin "6") (pinfunction "6_6") (pintype "passive"))
      (node (ref "U1") (pin "11") (pinfunction "11_11") (pintype "bidirectional"))
    )
    (net (code "30") (name "Net-(CON5-3)") (class "Default")
      (node (ref "C12") (pin "1") (pinfunction "1_1") (pintype "passive"))
      (node (ref "CON5") (pin "P$3") (pinfunction "3_P$3") (pintype "passive"))
      (node (ref "NTC1-7.4V") (pin "MP") (pinfunction "MP_MP") (pintype "passive"))
      (node (ref "R3") (pin "1") (pinfunction "1_1") (pintype "passive"))
      (node (ref "U1") (pin "18/A4") (pinfunction "18/A4_18/A4") (pintype "bidirectional"))
    )
    (net (code "31") (name "Net-(CON5-8)") (class "Default")
      (node (ref "CON5") (pin "P$8") (pinfunction "8_P$8") (pintype "passive"))
      (node (ref "R7") (pin "1") (pinfunction "1_1") (pintype "passive"))
    )
    (net (code "32") (name "Net-(CON5-10)") (class "Default")
      (node (ref "CON5") (pin "P$10") (pinfunction "10_P$10") (pintype "passive"))
      (node (ref "TO-FANBD") (pin "MP") (pinfunction "MP_MP") (pintype "passive"))
    )
    (net (code "33") (name "Net-(D1-PadA)") (class "Default")
      (node (ref "D1") (pin "A") (pinfunction "A_A") (pintype "passive"))
      (node (ref "TCO1") (pin "MP") (pinfunction "MP_MP") (pintype "passive"))
    )
    (net (code "34") (name "Net-(F2-1A)") (class "Default")
      (node (ref "F2") (pin "P$1") (pinfunction "1A_P$1") (pintype "passive"))
      (node (ref "TC02") (pin "MP") (pinfunction "MP_MP") (pintype "passive"))
    )
    (net (code "35") (name "Net-(FAN1B-S)") (class "Default")
      (node (ref "FAN1") (pin "2") (pinfunction "S_2") (pintype "passive"))
      (node (ref "HI-FAN") (pin "MP") (pinfunction "MP_MP") (pintype "passive"))
      (node (ref "R5") (pin "2") (pinfunction "2_2") (pintype "passive"))
    )
    (net (code "36") (name "Net-(IC1-ADJ)") (class "Default")
      (node (ref "C7") (pin "1") (pinfunction "1_1") (pintype "passive"))
      (node (ref "IC1") (pin "4") (pinfunction "ADJ_4") (pintype "passive"))
      (node (ref "R19") (pin "1") (pinfunction "1_1") (pintype "passive"))
    )
    (net (code "37") (name "Net-(IC1-OUT)") (class "Default")
      (node (ref "C11") (pin "1") (pinfunction "1_1") (pintype "passive"))
      (node (ref "C13") (pin "1") (pinfunction "1_1") (pintype "passive"))
      (node (ref "D3") (pin "A") (pinfunction "A_A") (pintype "passive"))
      (node (ref "IC1") (pin "5") (pinfunction "OUT_5") (pintype "output"))
      (node (ref "R19") (pin "2") (pinfunction "2_2") (pintype "passive"))
      (node (ref "TP+3.7V") (pin "MP") (pinfunction "MP_MP") (pintype "passive"))
    )
    (net (code "38") (name "Net-(IC2-IN)") (class "Default")
      (node (ref "C15") (pin "1") (pinfunction "1_1") (pintype "passive"))
      (node (ref "IC2") (pin "1") (pinfunction "IN_1") (pintype "input"))
      (node (ref "L1") (pin "1") (pinfunction "1_1") (pintype "passive"))
    )
    (net (code "39") (name "Net-(LD1-A)") (class "Default")
      (node (ref "LD1") (pin "1-ANODE") (pinfunction "A_1-ANODE") (pintype "passive"))
      (node (ref "R8") (pin "2") (pinfunction "2_2") (pintype "passive"))
    )
    (net (code "40") (name "Net-(LD2-A)") (class "Default")
      (node (ref "LD2") (pin "1-ANODE") (pinfunction "A_1-ANODE") (pintype "passive"))
      (node (ref "R9") (pin "2") (pinfunction "2_2") (pintype "passive"))
    )
    (net (code "41") (name "Net-(LD2-CG)") (class "Default")
      (node (ref "LD2") (pin "3-CATH-GRN") (pinfunction "CG_3-CATH-GRN") (pintype "passive"))
      (node (ref "U1") (pin "8") (pinfunction "8_8") (pintype "bidirectional"))
    )
    (net (code "42") (name "Net-(LD2-CR)") (class "Default")
      (node (ref "LD2") (pin "2-CATH-RED") (pinfunction "CR_2-CATH-RED") (pintype "passive"))
      (node (ref "U1") (pin "7") (pinfunction "7_7") (pintype "bidirectional"))
    )
    (net (code "43") (name "Net-(LD3-A)") (class "Default")
      (node (ref "LD3") (pin "ANODE") (pinfunction "A_ANODE") (pintype "passive"))
      (node (ref "R18") (pin "2") (pinfunction "2_2") (pintype "passive"))
    )
    (net (code "44") (name "Net-(NTC1-Pad1)") (class "Default")
      (node (ref "NTC1") (pin "1") (pinfunction "1_1") (pintype "passive"))
      (node (ref "R22") (pin "1") (pinfunction "1_1") (pintype "passive"))
      (node (ref "U1") (pin "17/A3") (pinfunction "17/A3_17/A3") (pintype "bidirectional"))
    )
    (net (code "45") (name "Net-(POT1-S)") (class "Default")
      (node (ref "POT1") (pin "2") (pinfunction "S_2") (pintype "passive"))
      (node (ref "U1") (pin "A10") (pinfunction "A10_A10") (pintype "input"))
    )
    (net (code "46") (name "Net-(Q1-D)") (class "Default")
      (node (ref "Q1") (pin "3") (pinfunction "D_3") (pintype "passive"))
      (node (ref "R5") (pin "1") (pinfunction "1_1") (pintype "passive"))
    )
    (net (code "47") (name "Net-(Q1-G)") (class "Default")
      (node (ref "Q1") (pin "1") (pinfunction "G_1") (pintype "passive"))
      (node (ref "R40") (pin "1") (pinfunction "1_1") (pintype "passive"))
    )
    (net (code "48") (name "Net-(Q2-G)") (class "Default")
      (node (ref "Q2") (pin "1") (pinfunction "G_1") (pintype "passive"))
      (node (ref "R1") (pin "1") (pinfunction "1_1") (pintype "passive"))
      (node (ref "T1") (pin "C") (pinfunction "C_C") (pintype "passive"))
    )
    (net (code "49") (name "Net-(Q3-D)") (class "Default")
      (node (ref "D2") (pin "C") (pinfunction "C_C") (pintype "passive"))
      (node (ref "Q3") (pin "3") (pinfunction "D_3") (pintype "passive"))
    )
    (net (code "50") (name "Net-(Q3-G)") (class "Default")
      (node (ref "Q3") (pin "1") (pinfunction "G_1") (pintype "passive"))
      (node (ref "R27") (pin "1") (pinfunction "1_1") (pintype "passive"))
    )
    (net (code "51") (name "Net-(Q5-G)") (class "Default")
      (node (ref "Q5") (pin "1") (pinfunction "G_1") (pintype "passive"))
      (node (ref "R14") (pin "1") (pinfunction "1_1") (pintype "passive"))
      (node (ref "T2") (pin "C") (pinfunction "C_C") (pintype "passive"))
    )
    (net (code "52") (name "Net-(R2-Pad1)") (class "Default")
      (node (ref "R2") (pin "1") (pinfunction "1_1") (pintype "passive"))
      (node (ref "T1") (pin "B") (pinfunction "B_B") (pintype "passive"))
    )
    (net (code "53") (name "PROT-3.7V") (class "Default")
      (node (ref "F1") (pin "P$1") (pinfunction "1A_P$1") (pintype "passive"))
      (node (ref "R28") (pin "1") (pinfunction "1_1") (pintype "passive"))
      (node (ref "R29") (pin "2") (pinfunction "2_2") (pintype "passive"))
      (node (ref "R30") (pin "1") (pinfunction "1_1") (pintype "passive"))
      (node (ref "R31") (pin "2") (pinfunction "2_2") (pintype "passive"))
      (node (ref "R32") (pin "1") (pinfunction "1_1") (pintype "passive"))
      (node (ref "R33") (pin "2") (pinfunction "2_2") (pintype "passive"))
      (node (ref "R34") (pin "1") (pinfunction "1_1") (pintype "passive"))
      (node (ref "R35") (pin "2") (pinfunction "2_2") (pintype "passive"))
      (node (ref "TPFUSE1A") (pin "MP") (pinfunction "MP_MP") (pintype "passive"))
    )
    (net (code "54") (name "PROT-7.4V") (class "Default")
      (node (ref "C1") (pin "1") (pinfunction "1_1") (pintype "passive"))
      (node (ref "C2") (pin "1") (pinfunction "1_1") (pintype "passive"))
      (node (ref "D1") (pin "C") (pinfunction "C_C") (pintype "passive"))
      (node (ref "FAN1") (pin "1") (pinfunction "S_1") (pintype "passive"))
      (node (ref "IC1") (pin "1") (pinfunction "IN_1") (pintype "input"))
      (node (ref "Q2") (pin "3") (pinfunction "S_3") (pintype "passive"))
      (node (ref "Q5") (pin "3") (pinfunction "S_3") (pintype "passive"))
      (node (ref "R1") (pin "2") (pinfunction "2_2") (pintype "passive"))
      (node (ref "R11") (pin "2") (pinfunction "2_2") (pintype "passive"))
      (node (ref "R14") (pin "2") (pinfunction "2_2") (pintype "passive"))
    )
    (net (code "55") (name "SCALED3.7V") (class "Default")
      (node (ref "C22") (pin "1") (pinfunction "1_1") (pintype "passive"))
      (node (ref "C5") (pin "1") (pinfunction "1_1") (pintype "passive"))
      (node (ref "CON2") (pin "P$4") (pinfunction "4_P$4") (pintype "passive"))
      (node (ref "R16") (pin "1") (pinfunction "1_1") (pintype "passive"))
      (node (ref "U1") (pin "22/A8") (pinfunction "22/A8_22/A8") (pintype "bidirectional"))
    )
    (net (code "56") (name "SCALED7.4V") (class "Default")
      (node (ref "C14") (pin "1") (pinfunction "1_1") (pintype "passive"))
      (node (ref "C21") (pin "1") (pinfunction "1_1") (pintype "passive"))
      (node (ref "CON5") (pin "P$7") (pinfunction "7_P$7") (pintype "passive"))
      (node (ref "R20") (pin "2") (pinfunction "2_2") (pintype "passive"))
      (node (ref "U1") (pin "23/A9") (pinfunction "23/A9_23/A9") (pintype "bidirectional"))
    )
    (net (code "57") (name "SCK") (class "Default")
      (node (ref "CON1") (pin "5") (pinfunction "5_5") (pintype "passive"))
      (node (ref "LD1") (pin "3-CATH-GRN") (pinfunction "CG_3-CATH-GRN") (pintype "passive"))
      (node (ref "U1") (pin "13") (pinfunction "13_13") (pintype "bidirectional"))
    )
    (net (code "58") (name "SW-LOW") (class "Default")
      (node (ref "D2") (pin "A") (pinfunction "A_A") (pintype "passive"))
      (node (ref "R29") (pin "1") (pinfunction "1_1") (pintype "passive"))
      (node (ref "R31") (pin "1") (pinfunction "1_1") (pintype "passive"))
      (node (ref "R33") (pin "1") (pinfunction "1_1") (pintype "passive"))
      (node (ref "R35") (pin "1") (pinfunction "1_1") (pintype "passive"))
      (node (ref "TP-LO-HEAT") (pin "MP") (pinfunction "MP_MP") (pintype "passive"))
    )
    (net (code "59") (name "SW-PROT-7.4V") (class "Default")
      (node (ref "Q2") (pin "2") (pinfunction "D_2") (pintype "passive"))
      (node (ref "R28") (pin "2") (pinfunction "2_2") (pintype "passive"))
      (node (ref "R30") (pin "2") (pinfunction "2_2") (pintype "passive"))
      (node (ref "R32") (pin "2") (pinfunction "2_2") (pintype "passive"))
      (node (ref "R34") (pin "2") (pinfunction "2_2") (pintype "passive"))
      (node (ref "TP-HI-HEAT") (pin "MP") (pinfunction "MP_MP") (pintype "passive"))
    )
    (net (code "60") (name "unconnected-(CON2-7-PadP$7)") (class "Default")
      (node (ref "CON2") (pin "P$7") (pinfunction "7_P$7") (pintype "passive"))
    )
  )
)
